# Keithley_2000_SCAN_Panasonic_DB25_V1_0.net
KiCad netlist of a schematic drawn in EasyEDA Pro
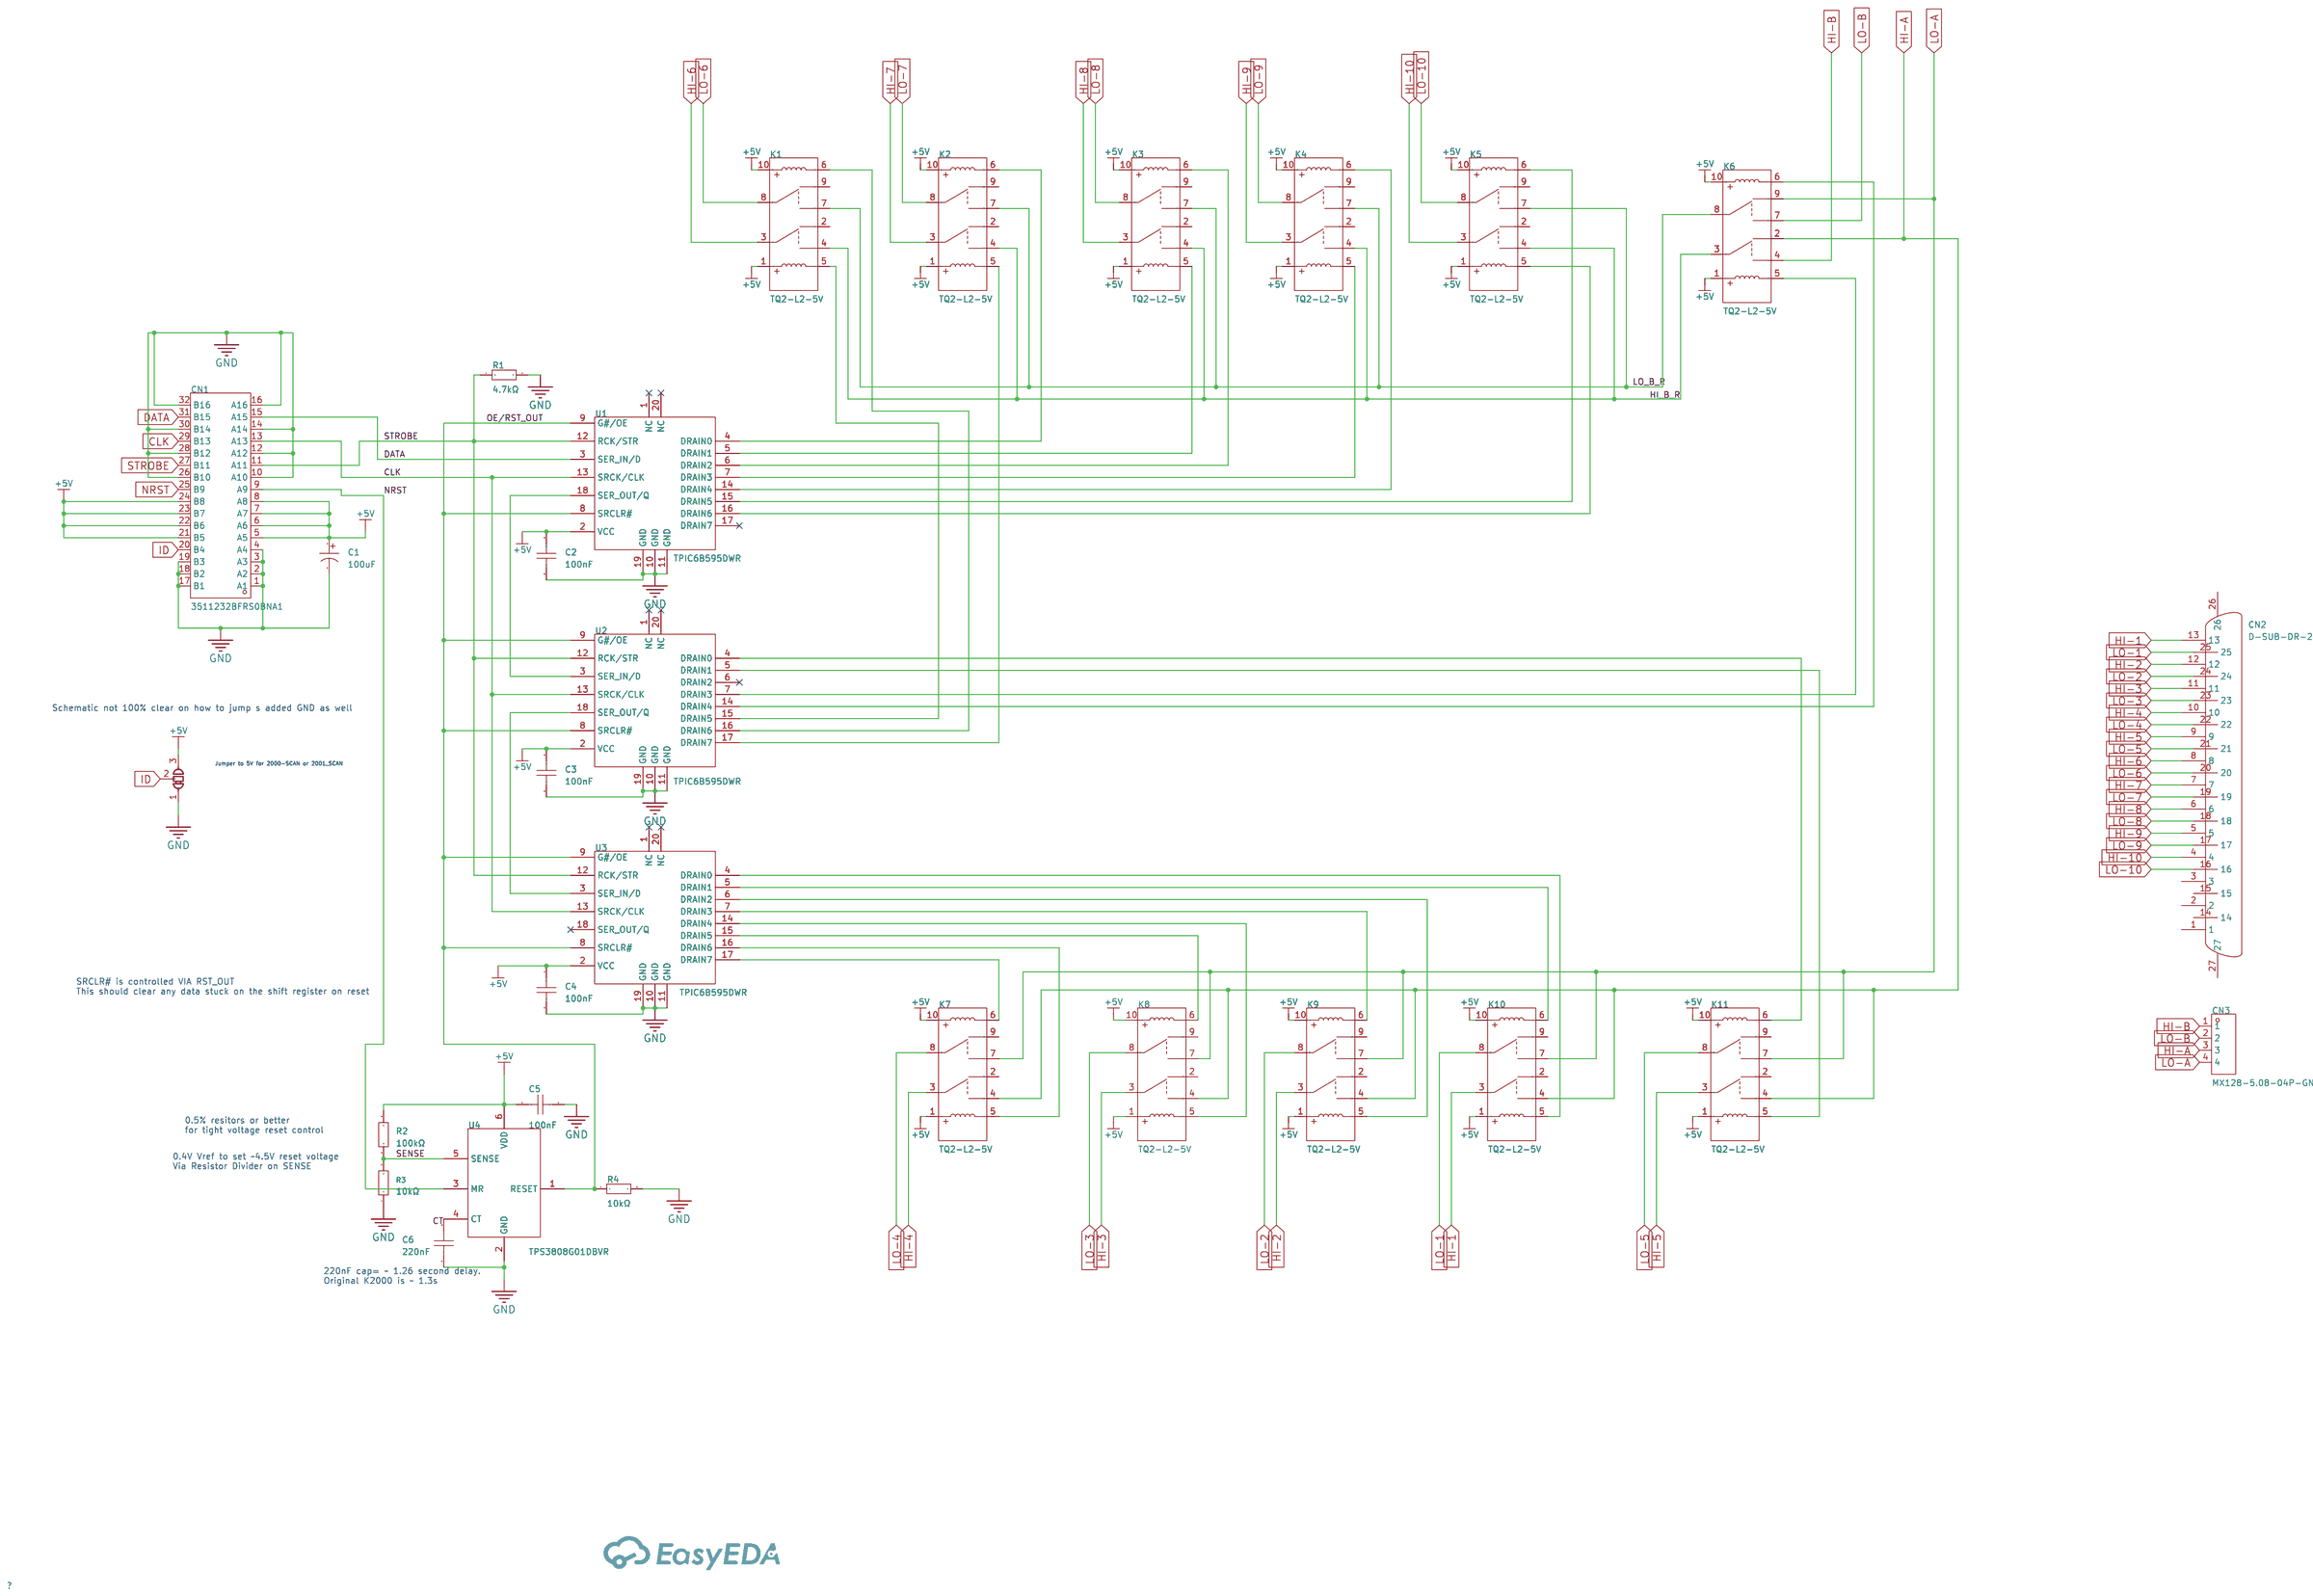
[diagram p0: schematic sheet]

(export (version "E")
  (design (tool "Eeschema 10.0.6"))
  (components
    (comp (ref "C1")
      (value "100uF")
      (footprint "easyedapro:CAP-TH_BD8.0-P3.50-D0.6-FD")
      (fields (field (name "Manufacturer Part") "ERJ1HM101F12OT") (field (name "Manufacturer") "AISHI(艾华集团)"))
      (libsource (lib "easyedapro") (part "ERJ1HM101F12OT"))
    )
    (comp (ref "C2")
      (value "100nF")
      (description "Capacitance:100nF Tolerance:±10% Tolerance:±10% Voltage Rating:50V Temperature Coefficient:X7R")
      (fields
        (field (name "Manufacturer Part") "CL10B104KB8NNNC")
        (field (name "Manufacturer") "SAMSUNG(三星)")
      )
      (libsource (lib "easyedapro") (part "CAP"))
    )
    (comp (ref "C3")
      (value "100nF")
      (description "Capacitance:100nF Tolerance:±10% Tolerance:±10% Voltage Rating:50V Temperature Coefficient:X7R")
      (fields
        (field (name "Manufacturer Part") "CL10B104KB8NNNC")
        (field (name "Manufacturer") "SAMSUNG(三星)")
      )
      (libsource (lib "easyedapro") (part "CAP"))
    )
    (comp (ref "C4")
      (value "100nF")
      (description "Capacitance:100nF Tolerance:±10% Tolerance:±10% Voltage Rating:50V Temperature Coefficient:X7R")
      (fields
        (field (name "Manufacturer Part") "CL10B104KB8NNNC")
        (field (name "Manufacturer") "SAMSUNG(三星)")
      )
      (libsource (lib "easyedapro") (part "CAP"))
    )
    (comp (ref "C5")
      (value "100nF")
      (description "Capacitance:100nF Tolerance:±10% Tolerance:±10% Voltage Rating:50V Temperature Coefficient:X7R")
      (fields
        (field (name "Manufacturer Part") "CL10B104KB8NNNC")
        (field (name "Manufacturer") "SAMSUNG(三星)")
      )
      (libsource (lib "easyedapro") (part "CAP"))
    )
    (comp (ref "C6")
      (value "220nF")
      (description "Capacitance:220nF Tolerance:±10% Tolerance:±10% Voltage Rating:25V Temperature Coefficient:X7R")
      (fields
        (field (name "Manufacturer Part") "CL10B224KA8NNNC")
        (field (name "Manufacturer") "SAMSUNG(三星)")
      )
      (libsource (lib "easyedapro") (part "CAP"))
    )
    (comp (ref "CN1")
      (value "3511232BFRS0BNA1")
      (footprint "easyedapro:CONN-TH_3511232BFRS0BNA1")
      (fields (field (name "Manufacturer") "JILN(锦凌)"))
      (libsource (lib "easyedapro") (part "3511232BFRS0BNA1"))
    )
    (comp (ref "CN2")
      (value "D-SUB-DR-25PCG-BB")
      (footprint "easyedapro:DB25-TH_D-SUB-DR-25PCG-BB")
      (fields (field (name "Manufacturer") "XUNPU(讯普)"))
      (libsource (lib "easyedapro") (part "D-SUB-DR-25PCG-BB"))
    )
    (comp (ref "CN3")
      (value "MX128-5.08-04P-GN01-Cu-Y-A")
      (footprint "easyedapro:CONN-TH_4P-P5.08_MX128-5.08-04P-GN01-CU-Y-A")
      (fields (field (name "Manufacturer") "MAX(迈旭)"))
      (libsource (lib "easyedapro") (part "MX128-5.08-04P-GN01-CU-Y-A"))
    )
    (comp (ref "JP1")
      (value "SolderJumper_3_Bridged12")
      (footprint "easyedapro:Jumper:SolderJumper-3_P1.3mm_Bridged12_Pad1.0x1.5mm_NumberLabels")
      (description "3-pole Solder Jumper, pins 1+2 closed/bridged")
      (libsource (lib "easyedapro") (part "Jumper_SolderJumper_3_Bridged12"))
    )
    (comp (ref "K1")
      (value "TQ2-L2-5V")
      (footprint "easyedapro:RELAY-TH_TQ2-L2-XXV")
      (fields (field (name "Manufacturer") "PANASONIC(松下)"))
      (libsource (lib "easyedapro") (part "TQ2-L2-5V"))
    )
    (comp (ref "K2")
      (value "TQ2-L2-5V")
      (footprint "easyedapro:RELAY-TH_TQ2-L2-XXV")
      (fields (field (name "Manufacturer") "PANASONIC(松下)"))
      (libsource (lib "easyedapro") (part "TQ2-L2-5V"))
    )
    (comp (ref "K3")
      (value "TQ2-L2-5V")
      (footprint "easyedapro:RELAY-TH_TQ2-L2-XXV")
      (fields (field (name "Manufacturer") "PANASONIC(松下)"))
      (libsource (lib "easyedapro") (part "TQ2-L2-5V"))
    )
    (comp (ref "K4")
      (value "TQ2-L2-5V")
      (footprint "easyedapro:RELAY-TH_TQ2-L2-XXV")
      (fields (field (name "Manufacturer") "PANASONIC(松下)"))
      (libsource (lib "easyedapro") (part "TQ2-L2-5V"))
    )
    (comp (ref "K5")
      (value "TQ2-L2-5V")
      (footprint "easyedapro:RELAY-TH_TQ2-L2-XXV")
      (fields (field (name "Manufacturer") "PANASONIC(松下)"))
      (libsource (lib "easyedapro") (part "TQ2-L2-5V"))
    )
    (comp (ref "K6")
      (value "TQ2-L2-5V")
      (footprint "easyedapro:RELAY-TH_TQ2-L2-XXV")
      (fields (field (name "Manufacturer") "PANASONIC(松下)"))
      (libsource (lib "easyedapro") (part "TQ2-L2-5V"))
    )
    (comp (ref "K7")
      (value "TQ2-L2-5V")
      (footprint "easyedapro:RELAY-TH_TQ2-L2-XXV")
      (fields (field (name "Manufacturer") "PANASONIC(松下)"))
      (libsource (lib "easyedapro") (part "TQ2-L2-5V"))
    )
    (comp (ref "K8")
      (value "TQ2-L2-5V")
      (footprint "easyedapro:RELAY-TH_TQ2-L2-XXV")
      (fields (field (name "Manufacturer") "PANASONIC(松下)"))
      (libsource (lib "easyedapro") (part "TQ2-L2-5V"))
    )
    (comp (ref "K9")
      (value "TQ2-L2-5V")
      (footprint "easyedapro:RELAY-TH_TQ2-L2-XXV")
      (fields (field (name "Manufacturer") "PANASONIC(松下)"))
      (libsource (lib "easyedapro") (part "TQ2-L2-5V"))
    )
    (comp (ref "K10")
      (value "TQ2-L2-5V")
      (footprint "easyedapro:RELAY-TH_TQ2-L2-XXV")
      (fields (field (name "Manufacturer") "PANASONIC(松下)"))
      (libsource (lib "easyedapro") (part "TQ2-L2-5V"))
    )
    (comp (ref "K11")
      (value "TQ2-L2-5V")
      (footprint "easyedapro:RELAY-TH_TQ2-L2-XXV")
      (fields (field (name "Manufacturer") "PANASONIC(松下)"))
      (libsource (lib "easyedapro") (part "TQ2-L2-5V"))
    )
    (comp (ref "R1")
      (value "4.7kΩ")
      (fields (field (name "Manufacturer Part") "RC0603FR-074K7L") (field (name "Manufacturer") "YAGEO(国巨)"))
      (libsource (lib "easyedapro") (part "Res"))
    )
    (comp (ref "R2")
      (value "100kΩ")
      (footprint "easyedapro:R0603")
      (fields (field (name "Manufacturer Part") "AR03DTCX1003") (field (name "Manufacturer") "Viking(光颉)"))
      (libsource (lib "easyedapro") (part "AR03DTCX1003"))
    )
    (comp (ref "R3")
      (value "10kΩ")
      (footprint "easyedapro:R0603")
      (fields
        (field (name "Manufacturer Part") "0603WAD1002T5E")
        (field (name "Manufacturer") "UNI-ROYAL(厚声)")
      )
      (libsource (lib "easyedapro") (part "0603WAD1002T5E"))
    )
    (comp (ref "R4")
      (value "10kΩ")
      (fields (field (name "Manufacturer Part") "RC0603FR-0710KL") (field (name "Manufacturer") "YAGEO(国巨)"))
      (libsource (lib "easyedapro") (part "Res"))
    )
    (comp (ref "U1")
      (value "TPIC6B595DWR")
      (footprint "easyedapro:SOIC-20_L13.0-W7.6-P1.27-LS10.3-BL")
      (fields (field (name "Manufacturer") "TI(德州仪器)"))
      (libsource (lib "easyedapro") (part "TPIC6B595DWR"))
    )
    (comp (ref "U2")
      (value "TPIC6B595DWR")
      (footprint "easyedapro:SOIC-20_L13.0-W7.6-P1.27-LS10.3-BL")
      (fields (field (name "Manufacturer") "TI(德州仪器)"))
      (libsource (lib "easyedapro") (part "TPIC6B595DWR"))
    )
    (comp (ref "U3")
      (value "TPIC6B595DWR")
      (footprint "easyedapro:SOIC-20_L13.0-W7.6-P1.27-LS10.3-BL")
      (fields (field (name "Manufacturer") "TI(德州仪器)"))
      (libsource (lib "easyedapro") (part "TPIC6B595DWR"))
    )
    (comp (ref "U4")
      (value "TPS3808G01DBVR")
      (footprint "easyedapro:SOT-23-6_L2.9-W1.6-P0.95-LS2.8-BR")
      (fields (field (name "Manufacturer") "TI(德州仪器)"))
      (libsource (lib "easyedapro") (part "TPS3808G01DBVR"))
    )
  )
  (nets
    (net (code "1") (name "+5V") (class "Default")
      (node (ref "C1") (pin "1") (pinfunction "1_1") (pintype "input"))
      (node (ref "C2") (pin "1") (pinfunction "1_1") (pintype "input"))
      (node (ref "C3") (pin "1") (pinfunction "1_1") (pintype "input"))
      (node (ref "C4") (pin "1") (pinfunction "1_1") (pintype "input"))
      (node (ref "C5") (pin "2") (pinfunction "2_2") (pintype "input"))
      (node (ref "CN1") (pin "21") (pinfunction "B5_21") (pintype "unspecified"))
      (node (ref "CN1") (pin "22") (pinfunction "B6_22") (pintype "unspecified"))
      (node (ref "CN1") (pin "23") (pinfunction "B7_23") (pintype "unspecified"))
      (node (ref "CN1") (pin "24") (pinfunction "B8_24") (pintype "unspecified"))
      (node (ref "CN1") (pin "5") (pinfunction "A5_5") (pintype "unspecified"))
      (node (ref "CN1") (pin "6") (pinfunction "A6_6") (pintype "unspecified"))
      (node (ref "CN1") (pin "7") (pinfunction "A7_7") (pintype "unspecified"))
      (node (ref "CN1") (pin "8") (pinfunction "A8_8") (pintype "unspecified"))
      (node (ref "JP1") (pin "3") (pinfunction "B_3") (pintype "unspecified"))
      (node (ref "K1") (pin "1") (pinfunction "1_1") (pintype "unspecified"))
      (node (ref "K1") (pin "10") (pinfunction "6_10") (pintype "unspecified"))
      (node (ref "K10") (pin "1") (pinfunction "1_1") (pintype "unspecified"))
      (node (ref "K10") (pin "10") (pinfunction "6_10") (pintype "unspecified"))
      (node (ref "K11") (pin "1") (pinfunction "1_1") (pintype "unspecified"))
      (node (ref "K11") (pin "10") (pinfunction "6_10") (pintype "unspecified"))
      (node (ref "K2") (pin "1") (pinfunction "1_1") (pintype "unspecified"))
      (node (ref "K2") (pin "10") (pinfunction "6_10") (pintype "unspecified"))
      (node (ref "K3") (pin "1") (pinfunction "1_1") (pintype "unspecified"))
      (node (ref "K3") (pin "10") (pinfunction "6_10") (pintype "unspecified"))
      (node (ref "K4") (pin "1") (pinfunction "1_1") (pintype "unspecified"))
      (node (ref "K4") (pin "10") (pinfunction "6_10") (pintype "unspecified"))
      (node (ref "K5") (pin "1") (pinfunction "1_1") (pintype "unspecified"))
      (node (ref "K5") (pin "10") (pinfunction "6_10") (pintype "unspecified"))
      (node (ref "K6") (pin "1") (pinfunction "1_1") (pintype "unspecified"))
      (node (ref "K6") (pin "10") (pinfunction "6_10") (pintype "unspecified"))
      (node (ref "K7") (pin "1") (pinfunction "1_1") (pintype "unspecified"))
      (node (ref "K7") (pin "10") (pinfunction "6_10") (pintype "unspecified"))
      (node (ref "K8") (pin "1") (pinfunction "1_1") (pintype "unspecified"))
      (node (ref "K8") (pin "10") (pinfunction "6_10") (pintype "unspecified"))
      (node (ref "K9") (pin "1") (pinfunction "1_1") (pintype "unspecified"))
      (node (ref "K9") (pin "10") (pinfunction "6_10") (pintype "unspecified"))
      (node (ref "R2") (pin "2") (pinfunction "2_2") (pintype "unspecified"))
      (node (ref "U1") (pin "2") (pinfunction "VCC_2") (pintype "unspecified"))
      (node (ref "U2") (pin "2") (pinfunction "VCC_2") (pintype "unspecified"))
      (node (ref "U3") (pin "2") (pinfunction "VCC_2") (pintype "unspecified"))
      (node (ref "U4") (pin "6") (pinfunction "VDD_6") (pintype "unspecified"))
    )
    (net (code "2") (name "/CT") (class "Default")
      (node (ref "C6") (pin "1") (pinfunction "1_1") (pintype "input"))
      (node (ref "U4") (pin "4") (pinfunction "CT_4") (pintype "unspecified"))
    )
    (net (code "3") (name "/HI_B_R") (class "Default")
      (node (ref "K1") (pin "4") (pinfunction "5_4") (pintype "unspecified"))
      (node (ref "K2") (pin "4") (pinfunction "5_4") (pintype "unspecified"))
      (node (ref "K3") (pin "4") (pinfunction "5_4") (pintype "unspecified"))
      (node (ref "K4") (pin "4") (pinfunction "5_4") (pintype "unspecified"))
      (node (ref "K5") (pin "4") (pinfunction "5_4") (pintype "unspecified"))
      (node (ref "K6") (pin "3") (pinfunction "4_3") (pintype "unspecified"))
    )
    (net (code "4") (name "/LO_B_R") (class "Default")
      (node (ref "K1") (pin "7") (pinfunction "8_7") (pintype "unspecified"))
      (node (ref "K2") (pin "7") (pinfunction "8_7") (pintype "unspecified"))
      (node (ref "K3") (pin "7") (pinfunction "8_7") (pintype "unspecified"))
      (node (ref "K4") (pin "7") (pinfunction "8_7") (pintype "unspecified"))
      (node (ref "K5") (pin "7") (pinfunction "8_7") (pintype "unspecified"))
      (node (ref "K6") (pin "8") (pinfunction "9_8") (pintype "unspecified"))
    )
    (net (code "5") (name "/OE{slash}RST_OUT") (class "Default")
      (node (ref "R4") (pin "1") (pinfunction "1_1") (pintype "input"))
      (node (ref "U1") (pin "8") (pinfunction "SRCLR#_8") (pintype "unspecified"))
      (node (ref "U1") (pin "9") (pinfunction "G#/OE_9") (pintype "unspecified"))
      (node (ref "U2") (pin "8") (pinfunction "SRCLR#_8") (pintype "unspecified"))
      (node (ref "U2") (pin "9") (pinfunction "G#/OE_9") (pintype "unspecified"))
      (node (ref "U3") (pin "8") (pinfunction "SRCLR#_8") (pintype "unspecified"))
      (node (ref "U3") (pin "9") (pinfunction "G#/OE_9") (pintype "unspecified"))
      (node (ref "U4") (pin "1") (pinfunction "RESET_1") (pintype "unspecified"))
    )
    (net (code "6") (name "/SENSE") (class "Default")
      (node (ref "R2") (pin "1") (pinfunction "1_1") (pintype "unspecified"))
      (node (ref "R3") (pin "2") (pinfunction "2_2") (pintype "input"))
      (node (ref "U4") (pin "5") (pinfunction "SENSE_5") (pintype "unspecified"))
    )
    (net (code "7") (name "CLK") (class "Default")
      (node (ref "CN1") (pin "13") (pinfunction "A13_13") (pintype "unspecified"))
      (node (ref "CN1") (pin "29") (pinfunction "B13_29") (pintype "unspecified"))
      (node (ref "U1") (pin "13") (pinfunction "SRCK/CLK_13") (pintype "unspecified"))
      (node (ref "U2") (pin "13") (pinfunction "SRCK/CLK_13") (pintype "unspecified"))
      (node (ref "U3") (pin "13") (pinfunction "SRCK/CLK_13") (pintype "unspecified"))
    )
    (net (code "8") (name "DATA") (class "Default")
      (node (ref "CN1") (pin "15") (pinfunction "A15_15") (pintype "unspecified"))
      (node (ref "CN1") (pin "31") (pinfunction "B15_31") (pintype "unspecified"))
      (node (ref "U1") (pin "3") (pinfunction "SER_IN/D_3") (pintype "unspecified"))
    )
    (net (code "9") (name "GND") (class "Default")
      (node (ref "C1") (pin "2") (pinfunction "2_2") (pintype "input"))
      (node (ref "C2") (pin "2") (pinfunction "2_2") (pintype "input"))
      (node (ref "C3") (pin "2") (pinfunction "2_2") (pintype "input"))
      (node (ref "C4") (pin "2") (pinfunction "2_2") (pintype "input"))
      (node (ref "C5") (pin "1") (pinfunction "1_1") (pintype "input"))
      (node (ref "C6") (pin "2") (pinfunction "2_2") (pintype "input"))
      (node (ref "CN1") (pin "1") (pinfunction "A1_1") (pintype "unspecified"))
      (node (ref "CN1") (pin "10") (pinfunction "A10_10") (pintype "unspecified"))
      (node (ref "CN1") (pin "12") (pinfunction "A12_12") (pintype "unspecified"))
      (node (ref "CN1") (pin "14") (pinfunction "A14_14") (pintype "unspecified"))
      (node (ref "CN1") (pin "16") (pinfunction "A16_16") (pintype "unspecified"))
      (node (ref "CN1") (pin "17") (pinfunction "B1_17") (pintype "unspecified"))
      (node (ref "CN1") (pin "18") (pinfunction "B2_18") (pintype "unspecified"))
      (node (ref "CN1") (pin "19") (pinfunction "B3_19") (pintype "unspecified"))
      (node (ref "CN1") (pin "2") (pinfunction "A2_2") (pintype "unspecified"))
      (node (ref "CN1") (pin "26") (pinfunction "B10_26") (pintype "unspecified"))
      (node (ref "CN1") (pin "28") (pinfunction "B12_28") (pintype "unspecified"))
      (node (ref "CN1") (pin "3") (pinfunction "A3_3") (pintype "unspecified"))
      (node (ref "CN1") (pin "30") (pinfunction "B14_30") (pintype "unspecified"))
      (node (ref "CN1") (pin "32") (pinfunction "B16_32") (pintype "unspecified"))
      (node (ref "CN1") (pin "4") (pinfunction "A4_4") (pintype "unspecified"))
      (node (ref "JP1") (pin "1") (pinfunction "A_1") (pintype "unspecified"))
      (node (ref "R1") (pin "2") (pinfunction "2_2") (pintype "input"))
      (node (ref "R3") (pin "1") (pinfunction "1_1") (pintype "input"))
      (node (ref "R4") (pin "2") (pinfunction "2_2") (pintype "input"))
      (node (ref "U1") (pin "10") (pinfunction "GND_10") (pintype "unspecified"))
      (node (ref "U1") (pin "11") (pinfunction "GND_11") (pintype "unspecified"))
      (node (ref "U1") (pin "19") (pinfunction "GND_19") (pintype "unspecified"))
      (node (ref "U2") (pin "10") (pinfunction "GND_10") (pintype "unspecified"))
      (node (ref "U2") (pin "11") (pinfunction "GND_11") (pintype "unspecified"))
      (node (ref "U2") (pin "19") (pinfunction "GND_19") (pintype "unspecified"))
      (node (ref "U3") (pin "10") (pinfunction "GND_10") (pintype "unspecified"))
      (node (ref "U3") (pin "11") (pinfunction "GND_11") (pintype "unspecified"))
      (node (ref "U3") (pin "19") (pinfunction "GND_19") (pintype "unspecified"))
      (node (ref "U4") (pin "2") (pinfunction "GND_2") (pintype "unspecified"))
    )
    (net (code "10") (name "HI-1") (class "Default")
      (node (ref "CN2") (pin "13") (pinfunction "13_13") (pintype "unspecified"))
      (node (ref "K10") (pin "3") (pinfunction "4_3") (pintype "unspecified"))
    )
    (net (code "11") (name "HI-2") (class "Default")
      (node (ref "CN2") (pin "12") (pinfunction "12_12") (pintype "unspecified"))
      (node (ref "K9") (pin "3") (pinfunction "4_3") (pintype "unspecified"))
    )
    (net (code "12") (name "HI-3") (class "Default")
      (node (ref "CN2") (pin "11") (pinfunction "11_11") (pintype "unspecified"))
      (node (ref "K8") (pin "3") (pinfunction "4_3") (pintype "unspecified"))
    )
    (net (code "13") (name "HI-4") (class "Default")
      (node (ref "CN2") (pin "10") (pinfunction "10_10") (pintype "unspecified"))
      (node (ref "K7") (pin "3") (pinfunction "4_3") (pintype "unspecified"))
    )
    (net (code "14") (name "HI-5") (class "Default")
      (node (ref "CN2") (pin "9") (pinfunction "9_9") (pintype "unspecified"))
      (node (ref "K11") (pin "3") (pinfunction "4_3") (pintype "unspecified"))
    )
    (net (code "15") (name "HI-6") (class "Default")
      (node (ref "CN2") (pin "8") (pinfunction "8_8") (pintype "unspecified"))
      (node (ref "K1") (pin "3") (pinfunction "4_3") (pintype "unspecified"))
    )
    (net (code "16") (name "HI-7") (class "Default")
      (node (ref "CN2") (pin "7") (pinfunction "7_7") (pintype "unspecified"))
      (node (ref "K2") (pin "3") (pinfunction "4_3") (pintype "unspecified"))
    )
    (net (code "17") (name "HI-8") (class "Default")
      (node (ref "CN2") (pin "6") (pinfunction "6_6") (pintype "unspecified"))
      (node (ref "K3") (pin "3") (pinfunction "4_3") (pintype "unspecified"))
    )
    (net (code "18") (name "HI-9") (class "Default")
      (node (ref "CN2") (pin "5") (pinfunction "5_5") (pintype "unspecified"))
      (node (ref "K4") (pin "3") (pinfunction "4_3") (pintype "unspecified"))
    )
    (net (code "19") (name "HI-10") (class "Default")
      (node (ref "CN2") (pin "4") (pinfunction "4_4") (pintype "unspecified"))
      (node (ref "K5") (pin "3") (pinfunction "4_3") (pintype "unspecified"))
    )
    (net (code "20") (name "HI-A") (class "Default")
      (node (ref "CN3") (pin "3") (pinfunction "3_3") (pintype "unspecified"))
      (node (ref "K10") (pin "4") (pinfunction "5_4") (pintype "unspecified"))
      (node (ref "K11") (pin "4") (pinfunction "5_4") (pintype "unspecified"))
      (node (ref "K6") (pin "2") (pinfunction "3_2") (pintype "unspecified"))
      (node (ref "K7") (pin "4") (pinfunction "5_4") (pintype "unspecified"))
      (node (ref "K8") (pin "4") (pinfunction "5_4") (pintype "unspecified"))
      (node (ref "K9") (pin "4") (pinfunction "5_4") (pintype "unspecified"))
    )
    (net (code "21") (name "HI-B") (class "Default")
      (node (ref "CN3") (pin "1") (pinfunction "1_1") (pintype "unspecified"))
      (node (ref "K6") (pin "4") (pinfunction "5_4") (pintype "unspecified"))
    )
    (net (code "22") (name "ID") (class "Default")
      (node (ref "CN1") (pin "20") (pinfunction "B4_20") (pintype "unspecified"))
      (node (ref "JP1") (pin "2") (pinfunction "C_2") (pintype "unspecified"))
    )
    (net (code "23") (name "LO-1") (class "Default")
      (node (ref "CN2") (pin "25") (pinfunction "25_25") (pintype "unspecified"))
      (node (ref "K10") (pin "8") (pinfunction "9_8") (pintype "unspecified"))
    )
    (net (code "24") (name "LO-2") (class "Default")
      (node (ref "CN2") (pin "24") (pinfunction "24_24") (pintype "unspecified"))
      (node (ref "K9") (pin "8") (pinfunction "9_8") (pintype "unspecified"))
    )
    (net (code "25") (name "LO-3") (class "Default")
      (node (ref "CN2") (pin "23") (pinfunction "23_23") (pintype "unspecified"))
      (node (ref "K8") (pin "8") (pinfunction "9_8") (pintype "unspecified"))
    )
    (net (code "26") (name "LO-4") (class "Default")
      (node (ref "CN2") (pin "22") (pinfunction "22_22") (pintype "unspecified"))
      (node (ref "K7") (pin "8") (pinfunction "9_8") (pintype "unspecified"))
    )
    (net (code "27") (name "LO-5") (class "Default")
      (node (ref "CN2") (pin "21") (pinfunction "21_21") (pintype "unspecified"))
      (node (ref "K11") (pin "8") (pinfunction "9_8") (pintype "unspecified"))
    )
    (net (code "28") (name "LO-6") (class "Default")
      (node (ref "CN2") (pin "20") (pinfunction "20_20") (pintype "unspecified"))
      (node (ref "K1") (pin "8") (pinfunction "9_8") (pintype "unspecified"))
    )
    (net (code "29") (name "LO-7") (class "Default")
      (node (ref "CN2") (pin "19") (pinfunction "19_19") (pintype "unspecified"))
      (node (ref "K2") (pin "8") (pinfunction "9_8") (pintype "unspecified"))
    )
    (net (code "30") (name "LO-8") (class "Default")
      (node (ref "CN2") (pin "18") (pinfunction "18_18") (pintype "unspecified"))
      (node (ref "K3") (pin "8") (pinfunction "9_8") (pintype "unspecified"))
    )
    (net (code "31") (name "LO-9") (class "Default")
      (node (ref "CN2") (pin "17") (pinfunction "17_17") (pintype "unspecified"))
      (node (ref "K4") (pin "8") (pinfunction "9_8") (pintype "unspecified"))
    )
    (net (code "32") (name "LO-10") (class "Default")
      (node (ref "CN2") (pin "16") (pinfunction "16_16") (pintype "unspecified"))
      (node (ref "K5") (pin "8") (pinfunction "9_8") (pintype "unspecified"))
    )
    (net (code "33") (name "LO-A") (class "Default")
      (node (ref "CN3") (pin "4") (pinfunction "4_4") (pintype "unspecified"))
      (node (ref "K10") (pin "7") (pinfunction "8_7") (pintype "unspecified"))
      (node (ref "K11") (pin "7") (pinfunction "8_7") (pintype "unspecified"))
      (node (ref "K6") (pin "9") (pinfunction "10_9") (pintype "unspecified"))
      (node (ref "K7") (pin "7") (pinfunction "8_7") (pintype "unspecified"))
      (node (ref "K8") (pin "7") (pinfunction "8_7") (pintype "unspecified"))
      (node (ref "K9") (pin "7") (pinfunction "8_7") (pintype "unspecified"))
    )
    (net (code "34") (name "LO-B") (class "Default")
      (node (ref "CN3") (pin "2") (pinfunction "2_2") (pintype "unspecified"))
      (node (ref "K6") (pin "7") (pinfunction "8_7") (pintype "unspecified"))
    )
    (net (code "35") (name "NRST") (class "Default")
      (node (ref "CN1") (pin "25") (pinfunction "B9_25") (pintype "unspecified"))
      (node (ref "CN1") (pin "9") (pinfunction "A9_9") (pintype "unspecified"))
      (node (ref "U4") (pin "3") (pinfunction "MR_3") (pintype "unspecified"))
    )
    (net (code "36") (name "Net-(K1-7)") (class "Default")
      (node (ref "K1") (pin "6") (pinfunction "7_6") (pintype "unspecified"))
      (node (ref "U2") (pin "16") (pinfunction "DRAIN6_16") (pintype "unspecified"))
    )
    (net (code "37") (name "Net-(K1-12)") (class "Default")
      (node (ref "K1") (pin "5") (pinfunction "12_5") (pintype "unspecified"))
      (node (ref "U2") (pin "15") (pinfunction "DRAIN5_15") (pintype "unspecified"))
    )
    (net (code "38") (name "Net-(K2-7)") (class "Default")
      (node (ref "K2") (pin "6") (pinfunction "7_6") (pintype "unspecified"))
      (node (ref "U1") (pin "4") (pinfunction "DRAIN0_4") (pintype "unspecified"))
    )
    (net (code "39") (name "Net-(K2-12)") (class "Default")
      (node (ref "K2") (pin "5") (pinfunction "12_5") (pintype "unspecified"))
      (node (ref "U2") (pin "17") (pinfunction "DRAIN7_17") (pintype "unspecified"))
    )
    (net (code "40") (name "Net-(K3-7)") (class "Default")
      (node (ref "K3") (pin "6") (pinfunction "7_6") (pintype "unspecified"))
      (node (ref "U1") (pin "6") (pinfunction "DRAIN2_6") (pintype "unspecified"))
    )
    (net (code "41") (name "Net-(K3-12)") (class "Default")
      (node (ref "K3") (pin "5") (pinfunction "12_5") (pintype "unspecified"))
      (node (ref "U1") (pin "5") (pinfunction "DRAIN1_5") (pintype "unspecified"))
    )
    (net (code "42") (name "Net-(K4-7)") (class "Default")
      (node (ref "K4") (pin "6") (pinfunction "7_6") (pintype "unspecified"))
      (node (ref "U1") (pin "14") (pinfunction "DRAIN4_14") (pintype "unspecified"))
    )
    (net (code "43") (name "Net-(K4-12)") (class "Default")
      (node (ref "K4") (pin "5") (pinfunction "12_5") (pintype "unspecified"))
      (node (ref "U1") (pin "7") (pinfunction "DRAIN3_7") (pintype "unspecified"))
    )
    (net (code "44") (name "Net-(K5-7)") (class "Default")
      (node (ref "K5") (pin "6") (pinfunction "7_6") (pintype "unspecified"))
      (node (ref "U1") (pin "15") (pinfunction "DRAIN5_15") (pintype "unspecified"))
    )
    (net (code "45") (name "Net-(K5-12)") (class "Default")
      (node (ref "K5") (pin "5") (pinfunction "12_5") (pintype "unspecified"))
      (node (ref "U1") (pin "16") (pinfunction "DRAIN6_16") (pintype "unspecified"))
    )
    (net (code "46") (name "Net-(K6-7)") (class "Default")
      (node (ref "K6") (pin "6") (pinfunction "7_6") (pintype "unspecified"))
      (node (ref "U2") (pin "14") (pinfunction "DRAIN4_14") (pintype "unspecified"))
    )
    (net (code "47") (name "Net-(K6-12)") (class "Default")
      (node (ref "K6") (pin "5") (pinfunction "12_5") (pintype "unspecified"))
      (node (ref "U2") (pin "7") (pinfunction "DRAIN3_7") (pintype "unspecified"))
    )
    (net (code "48") (name "Net-(K7-7)") (class "Default")
      (node (ref "K7") (pin "6") (pinfunction "7_6") (pintype "unspecified"))
      (node (ref "U3") (pin "17") (pinfunction "DRAIN7_17") (pintype "unspecified"))
    )
    (net (code "49") (name "Net-(K7-12)") (class "Default")
      (node (ref "K7") (pin "5") (pinfunction "12_5") (pintype "unspecified"))
      (node (ref "U3") (pin "16") (pinfunction "DRAIN6_16") (pintype "unspecified"))
    )
    (net (code "50") (name "Net-(K8-7)") (class "Default")
      (node (ref "K8") (pin "6") (pinfunction "7_6") (pintype "unspecified"))
      (node (ref "U3") (pin "15") (pinfunction "DRAIN5_15") (pintype "unspecified"))
    )
    (net (code "51") (name "Net-(K8-12)") (class "Default")
      (node (ref "K8") (pin "5") (pinfunction "12_5") (pintype "unspecified"))
      (node (ref "U3") (pin "14") (pinfunction "DRAIN4_14") (pintype "unspecified"))
    )
    (net (code "52") (name "Net-(K9-7)") (class "Default")
      (node (ref "K9") (pin "6") (pinfunction "7_6") (pintype "unspecified"))
      (node (ref "U3") (pin "7") (pinfunction "DRAIN3_7") (pintype "unspecified"))
    )
    (net (code "53") (name "Net-(K9-12)") (class "Default")
      (node (ref "K9") (pin "5") (pinfunction "12_5") (pintype "unspecified"))
      (node (ref "U3") (pin "6") (pinfunction "DRAIN2_6") (pintype "unspecified"))
    )
    (net (code "54") (name "Net-(K10-7)") (class "Default")
      (node (ref "K10") (pin "6") (pinfunction "7_6") (pintype "unspecified"))
      (node (ref "U3") (pin "5") (pinfunction "DRAIN1_5") (pintype "unspecified"))
    )
    (net (code "55") (name "Net-(K10-12)") (class "Default")
      (node (ref "K10") (pin "5") (pinfunction "12_5") (pintype "unspecified"))
      (node (ref "U3") (pin "4") (pinfunction "DRAIN0_4") (pintype "unspecified"))
    )
    (net (code "56") (name "Net-(K11-7)") (class "Default")
      (node (ref "K11") (pin "6") (pinfunction "7_6") (pintype "unspecified"))
      (node (ref "U2") (pin "4") (pinfunction "DRAIN0_4") (pintype "unspecified"))
    )
    (net (code "57") (name "Net-(K11-12)") (class "Default")
      (node (ref "K11") (pin "5") (pinfunction "12_5") (pintype "unspecified"))
      (node (ref "U2") (pin "5") (pinfunction "DRAIN1_5") (pintype "unspecified"))
    )
    (net (code "58") (name "Net-(U1-SER_OUT{slash}Q)") (class "Default")
      (node (ref "U1") (pin "18") (pinfunction "SER_OUT/Q_18") (pintype "unspecified"))
      (node (ref "U2") (pin "3") (pinfunction "SER_IN/D_3") (pintype "unspecified"))
    )
    (net (code "59") (name "Net-(U2-SER_OUT{slash}Q)") (class "Default")
      (node (ref "U2") (pin "18") (pinfunction "SER_OUT/Q_18") (pintype "unspecified"))
      (node (ref "U3") (pin "3") (pinfunction "SER_IN/D_3") (pintype "unspecified"))
    )
    (net (code "60") (name "STROBE") (class "Default")
      (node (ref "CN1") (pin "11") (pinfunction "A11_11") (pintype "unspecified"))
      (node (ref "CN1") (pin "27") (pinfunction "B11_27") (pintype "unspecified"))
      (node (ref "R1") (pin "1") (pinfunction "1_1") (pintype "input"))
      (node (ref "U1") (pin "12") (pinfunction "RCK/STR_12") (pintype "unspecified"))
      (node (ref "U2") (pin "12") (pinfunction "RCK/STR_12") (pintype "unspecified"))
      (node (ref "U3") (pin "12") (pinfunction "RCK/STR_12") (pintype "unspecified"))
    )
    (net (code "61") (name "unconnected-(CN2-Pad1)") (class "Default")
      (node (ref "CN2") (pin "1") (pinfunction "1_1") (pintype "unspecified"))
    )
    (net (code "62") (name "unconnected-(CN2-Pad2)") (class "Default")
      (node (ref "CN2") (pin "2") (pinfunction "2_2") (pintype "unspecified"))
    )
    (net (code "63") (name "unconnected-(CN2-Pad3)") (class "Default")
      (node (ref "CN2") (pin "3") (pinfunction "3_3") (pintype "unspecified"))
    )
    (net (code "64") (name "unconnected-(CN2-Pad14)") (class "Default")
      (node (ref "CN2") (pin "14") (pinfunction "14_14") (pintype "unspecified"))
    )
    (net (code "65") (name "unconnected-(CN2-Pad15)") (class "Default")
      (node (ref "CN2") (pin "15") (pinfunction "15_15") (pintype "unspecified"))
    )
    (net (code "66") (name "unconnected-(CN2-Pad26)") (class "Default")
      (node (ref "CN2") (pin "26") (pinfunction "26_26") (pintype "unspecified"))
    )
    (net (code "67") (name "unconnected-(CN2-Pad27)") (class "Default")
      (node (ref "CN2") (pin "27") (pinfunction "27_27") (pintype "unspecified"))
    )
    (net (code "68") (name "unconnected-(K1-3-Pad2)") (class "Default")
      (node (ref "K1") (pin "2") (pinfunction "3_2") (pintype "unspecified"))
    )
    (net (code "69") (name "unconnected-(K1-10-Pad9)") (class "Default")
      (node (ref "K1") (pin "9") (pinfunction "10_9") (pintype "unspecified"))
    )
    (net (code "70") (name "unconnected-(K2-3-Pad2)") (class "Default")
      (node (ref "K2") (pin "2") (pinfunction "3_2") (pintype "unspecified"))
    )
    (net (code "71") (name "unconnected-(K2-10-Pad9)") (class "Default")
      (node (ref "K2") (pin "9") (pinfunction "10_9") (pintype "unspecified"))
    )
    (net (code "72") (name "unconnected-(K3-3-Pad2)") (class "Default")
      (node (ref "K3") (pin "2") (pinfunction "3_2") (pintype "unspecified"))
    )
    (net (code "73") (name "unconnected-(K3-10-Pad9)") (class "Default")
      (node (ref "K3") (pin "9") (pinfunction "10_9") (pintype "unspecified"))
    )
    (net (code "74") (name "unconnected-(K4-3-Pad2)") (class "Default")
      (node (ref "K4") (pin "2") (pinfunction "3_2") (pintype "unspecified"))
    )
    (net (code "75") (name "unconnected-(K4-10-Pad9)") (class "Default")
      (node (ref "K4") (pin "9") (pinfunction "10_9") (pintype "unspecified"))
    )
    (net (code "76") (name "unconnected-(K5-3-Pad2)") (class "Default")
      (node (ref "K5") (pin "2") (pinfunction "3_2") (pintype "unspecified"))
    )
    (net (code "77") (name "unconnected-(K5-10-Pad9)") (class "Default")
      (node (ref "K5") (pin "9") (pinfunction "10_9") (pintype "unspecified"))
    )
    (net (code "78") (name "unconnected-(K7-3-Pad2)") (class "Default")
      (node (ref "K7") (pin "2") (pinfunction "3_2") (pintype "unspecified"))
    )
    (net (code "79") (name "unconnected-(K7-10-Pad9)") (class "Default")
      (node (ref "K7") (pin "9") (pinfunction "10_9") (pintype "unspecified"))
    )
    (net (code "80") (name "unconnected-(K8-3-Pad2)") (class "Default")
      (node (ref "K8") (pin "2") (pinfunction "3_2") (pintype "unspecified"))
    )
    (net (code "81") (name "unconnected-(K8-10-Pad9)") (class "Default")
      (node (ref "K8") (pin "9") (pinfunction "10_9") (pintype "unspecified"))
    )
    (net (code "82") (name "unconnected-(K9-3-Pad2)") (class "Default")
      (node (ref "K9") (pin "2") (pinfunction "3_2") (pintype "unspecified"))
    )
    (net (code "83") (name "unconnected-(K9-10-Pad9)") (class "Default")
      (node (ref "K9") (pin "9") (pinfunction "10_9") (pintype "unspecified"))
    )
    (net (code "84") (name "unconnected-(K10-3-Pad2)") (class "Default")
      (node (ref "K10") (pin "2") (pinfunction "3_2") (pintype "unspecified"))
    )
    (net (code "85") (name "unconnected-(K10-10-Pad9)") (class "Default")
      (node (ref "K10") (pin "9") (pinfunction "10_9") (pintype "unspecified"))
    )
    (net (code "86") (name "unconnected-(K11-3-Pad2)") (class "Default")
      (node (ref "K11") (pin "2") (pinfunction "3_2") (pintype "unspecified"))
    )
    (net (code "87") (name "unconnected-(K11-10-Pad9)") (class "Default")
      (node (ref "K11") (pin "9") (pinfunction "10_9") (pintype "unspecified"))
    )
    (net (code "88") (name "unconnected-(U1-DRAIN7-Pad17)") (class "Default")
      (node (ref "U1") (pin "17") (pinfunction "DRAIN7_17") (pintype "unspecified+no_connect"))
    )
    (net (code "89") (name "unconnected-(U1-NC-Pad1)") (class "Default")
      (node (ref "U1") (pin "1") (pinfunction "NC_1") (pintype "unspecified+no_connect"))
    )
    (net (code "90") (name "unconnected-(U1-NC-Pad20)") (class "Default")
      (node (ref "U1") (pin "20") (pinfunction "NC_20") (pintype "unspecified+no_connect"))
    )
    (net (code "91") (name "unconnected-(U2-DRAIN2-Pad6)") (class "Default")
      (node (ref "U2") (pin "6") (pinfunction "DRAIN2_6") (pintype "unspecified+no_connect"))
    )
    (net (code "92") (name "unconnected-(U2-NC-Pad1)") (class "Default")
      (node (ref "U2") (pin "1") (pinfunction "NC_1") (pintype "unspecified+no_connect"))
    )
    (net (code "93") (name "unconnected-(U2-NC-Pad20)") (class "Default")
      (node (ref "U2") (pin "20") (pinfunction "NC_20") (pintype "unspecified+no_connect"))
    )
    (net (code "94") (name "unconnected-(U3-NC-Pad1)") (class "Default")
      (node (ref "U3") (pin "1") (pinfunction "NC_1") (pintype "unspecified+no_connect"))
    )
    (net (code "95") (name "unconnected-(U3-NC-Pad20)") (class "Default")
      (node (ref "U3") (pin "20") (pinfunction "NC_20") (pintype "unspecified+no_connect"))
    )
    (net (code "96") (name "unconnected-(U3-SER_OUT{slash}Q-Pad18)") (class "Default")
      (node (ref "U3") (pin "18") (pinfunction "SER_OUT/Q_18") (pintype "unspecified+no_connect"))
    )
  )
)
